# eNode_Spark.net
KiCad netlist of a schematic drawn in EAGLE
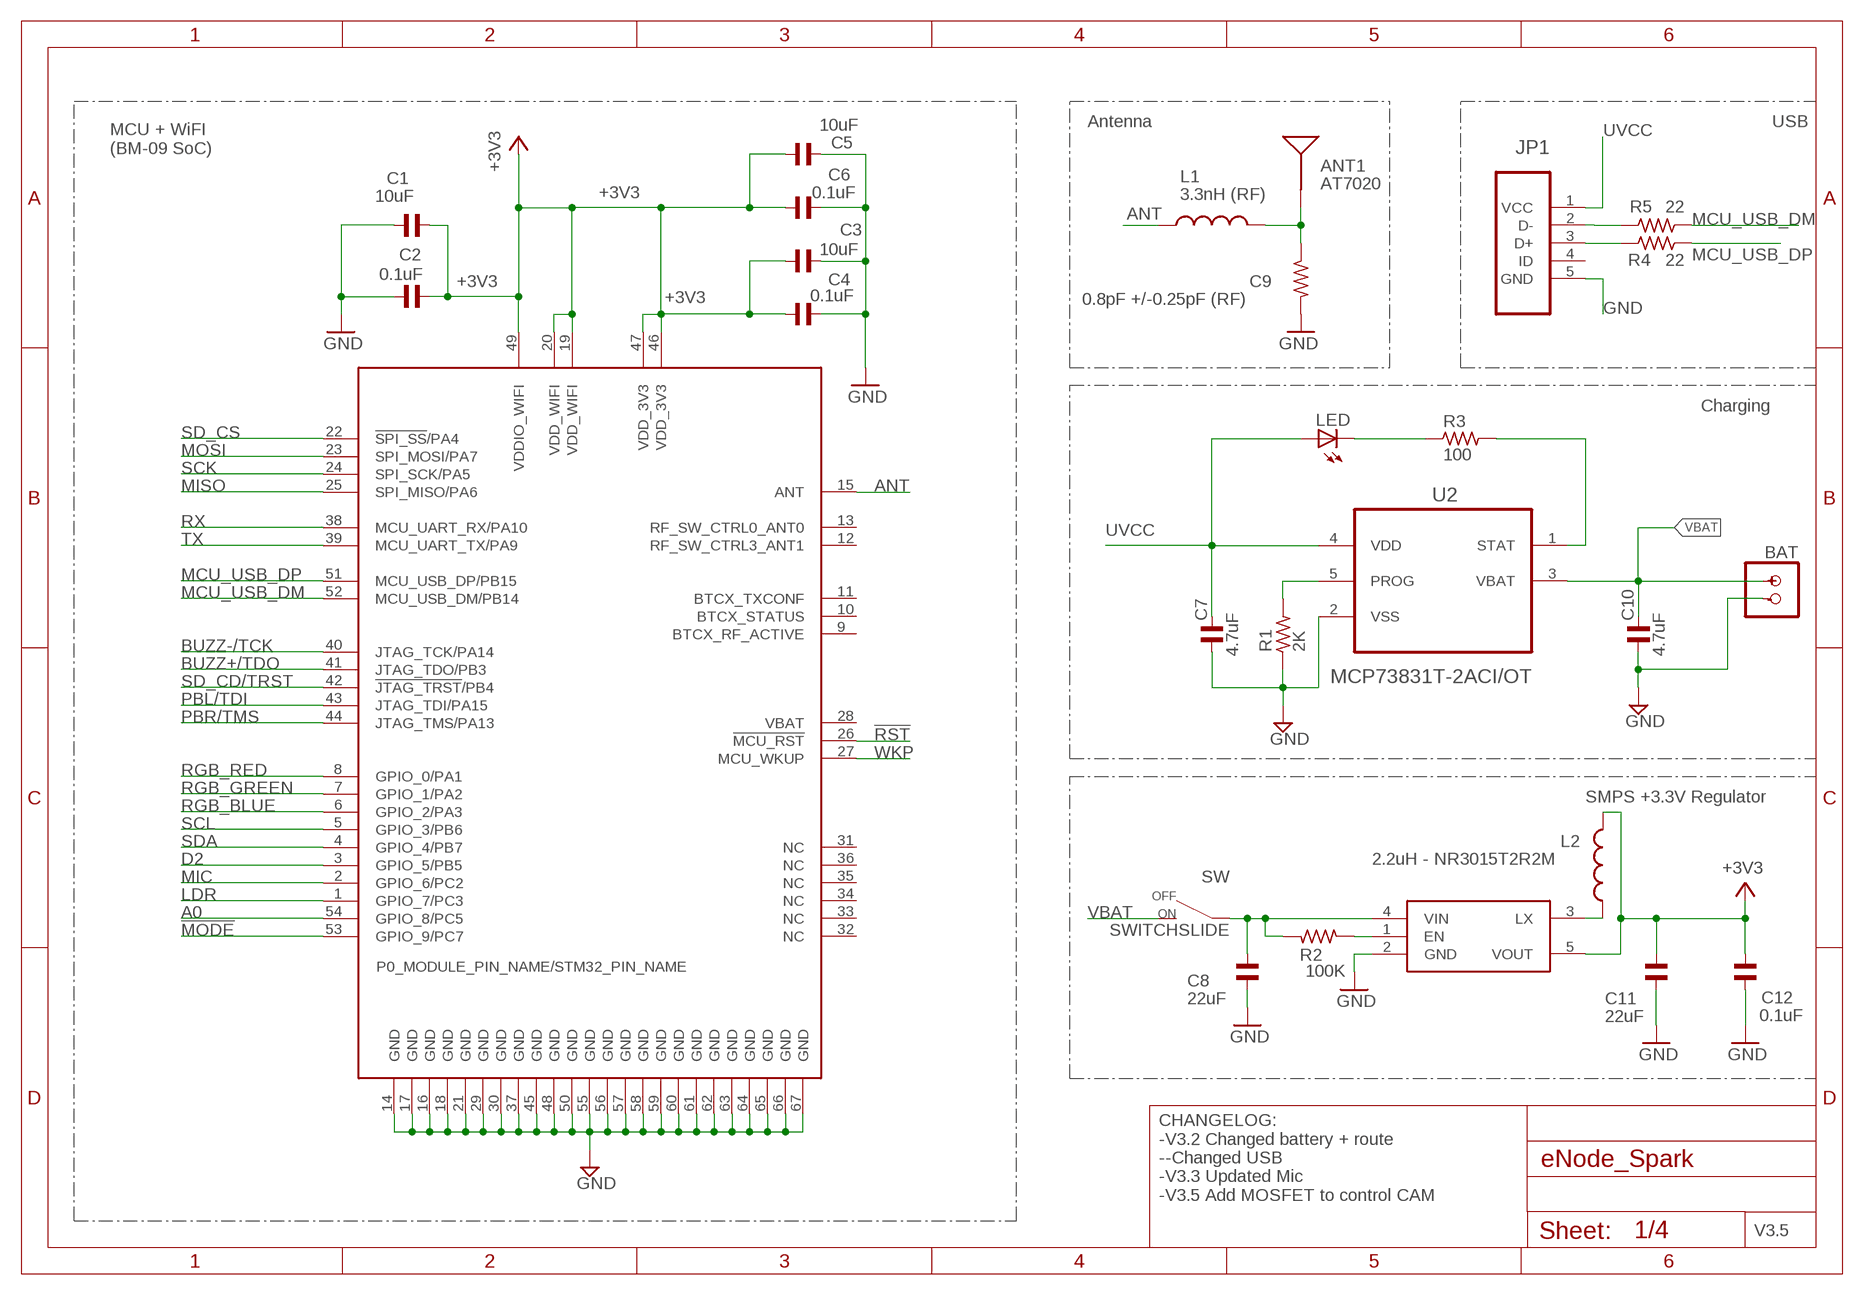
[diagram p0: schematic, sheet 1]
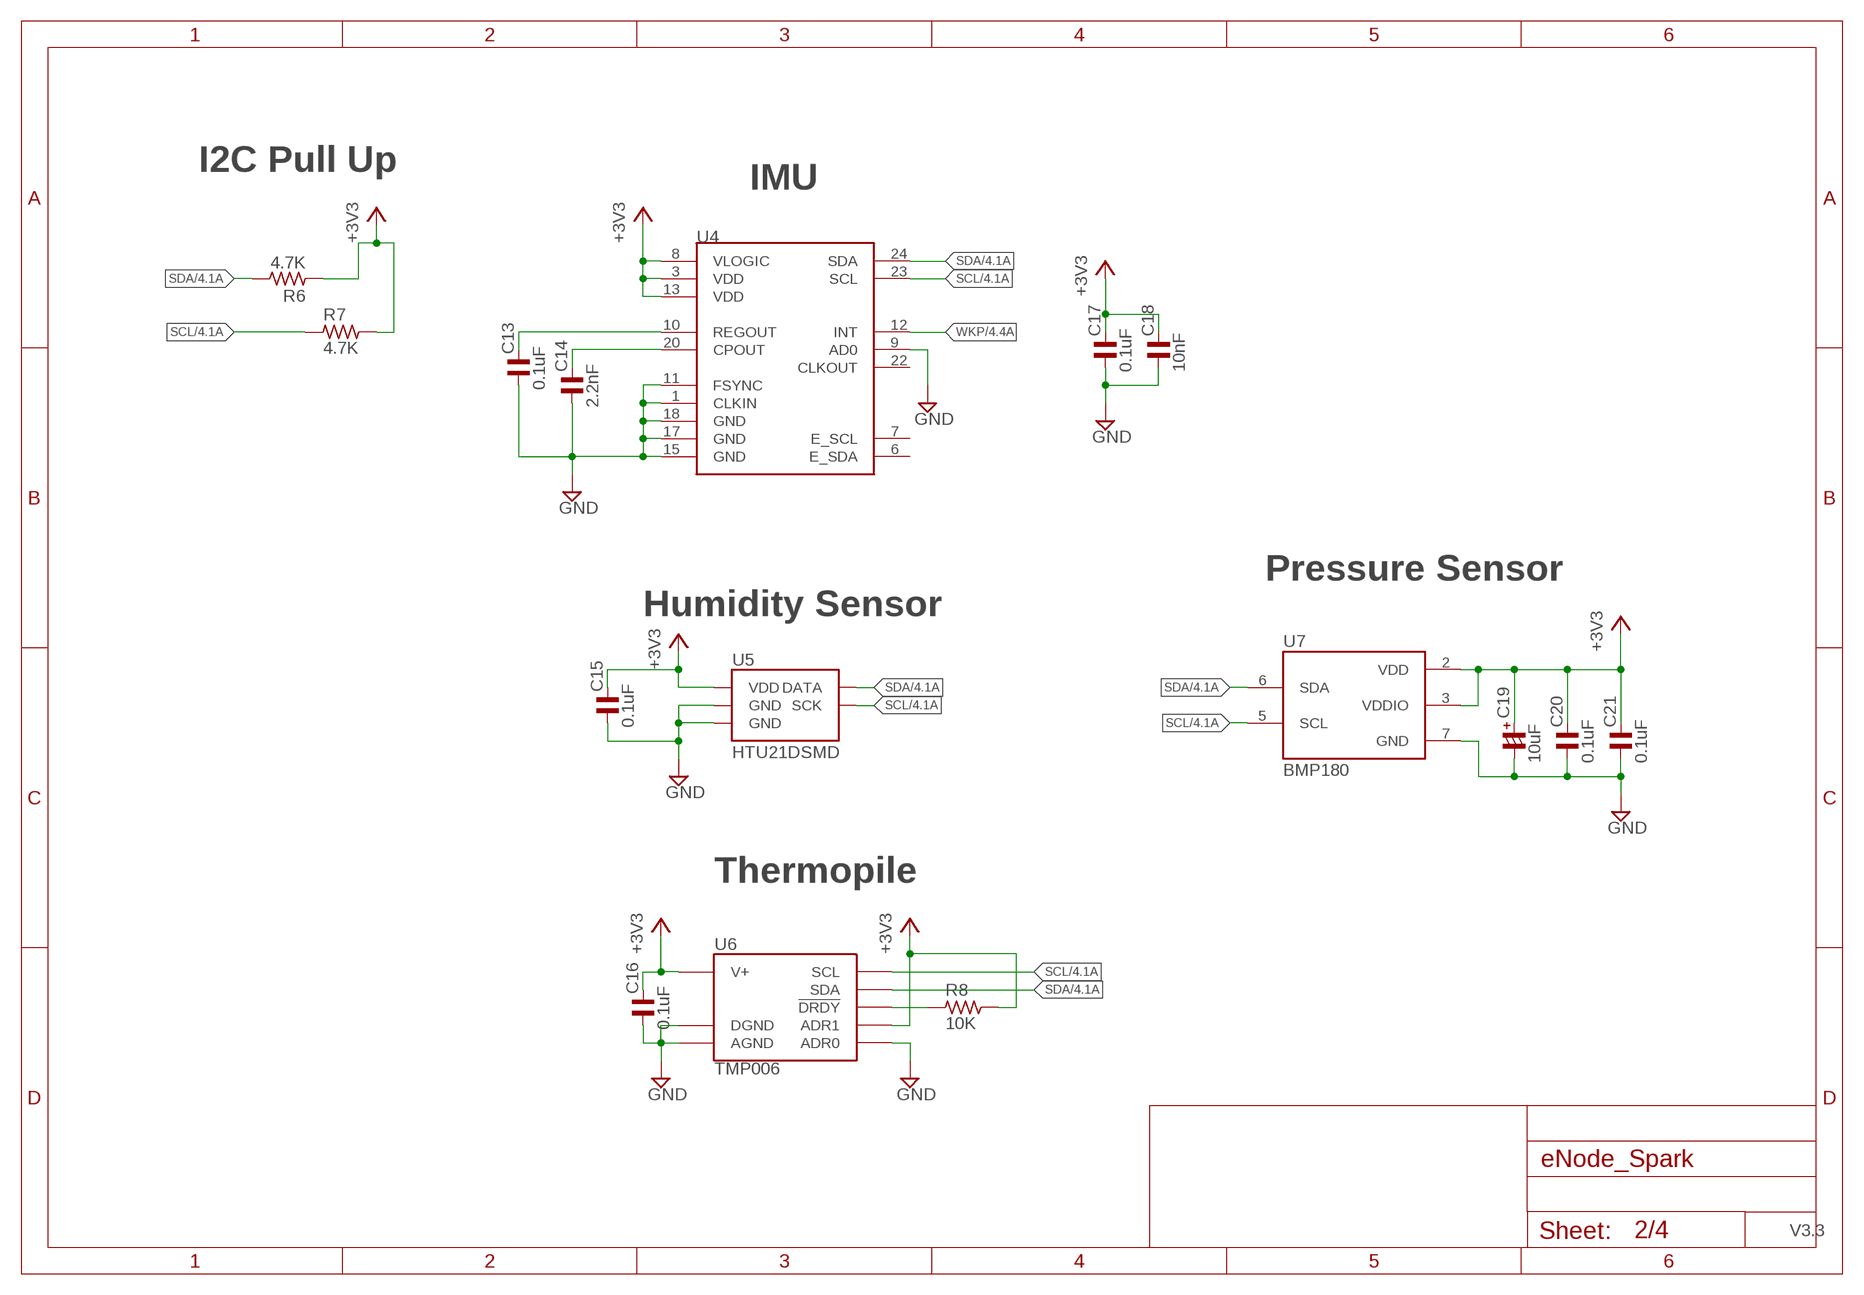
[diagram p1: schematic, sheet 2]
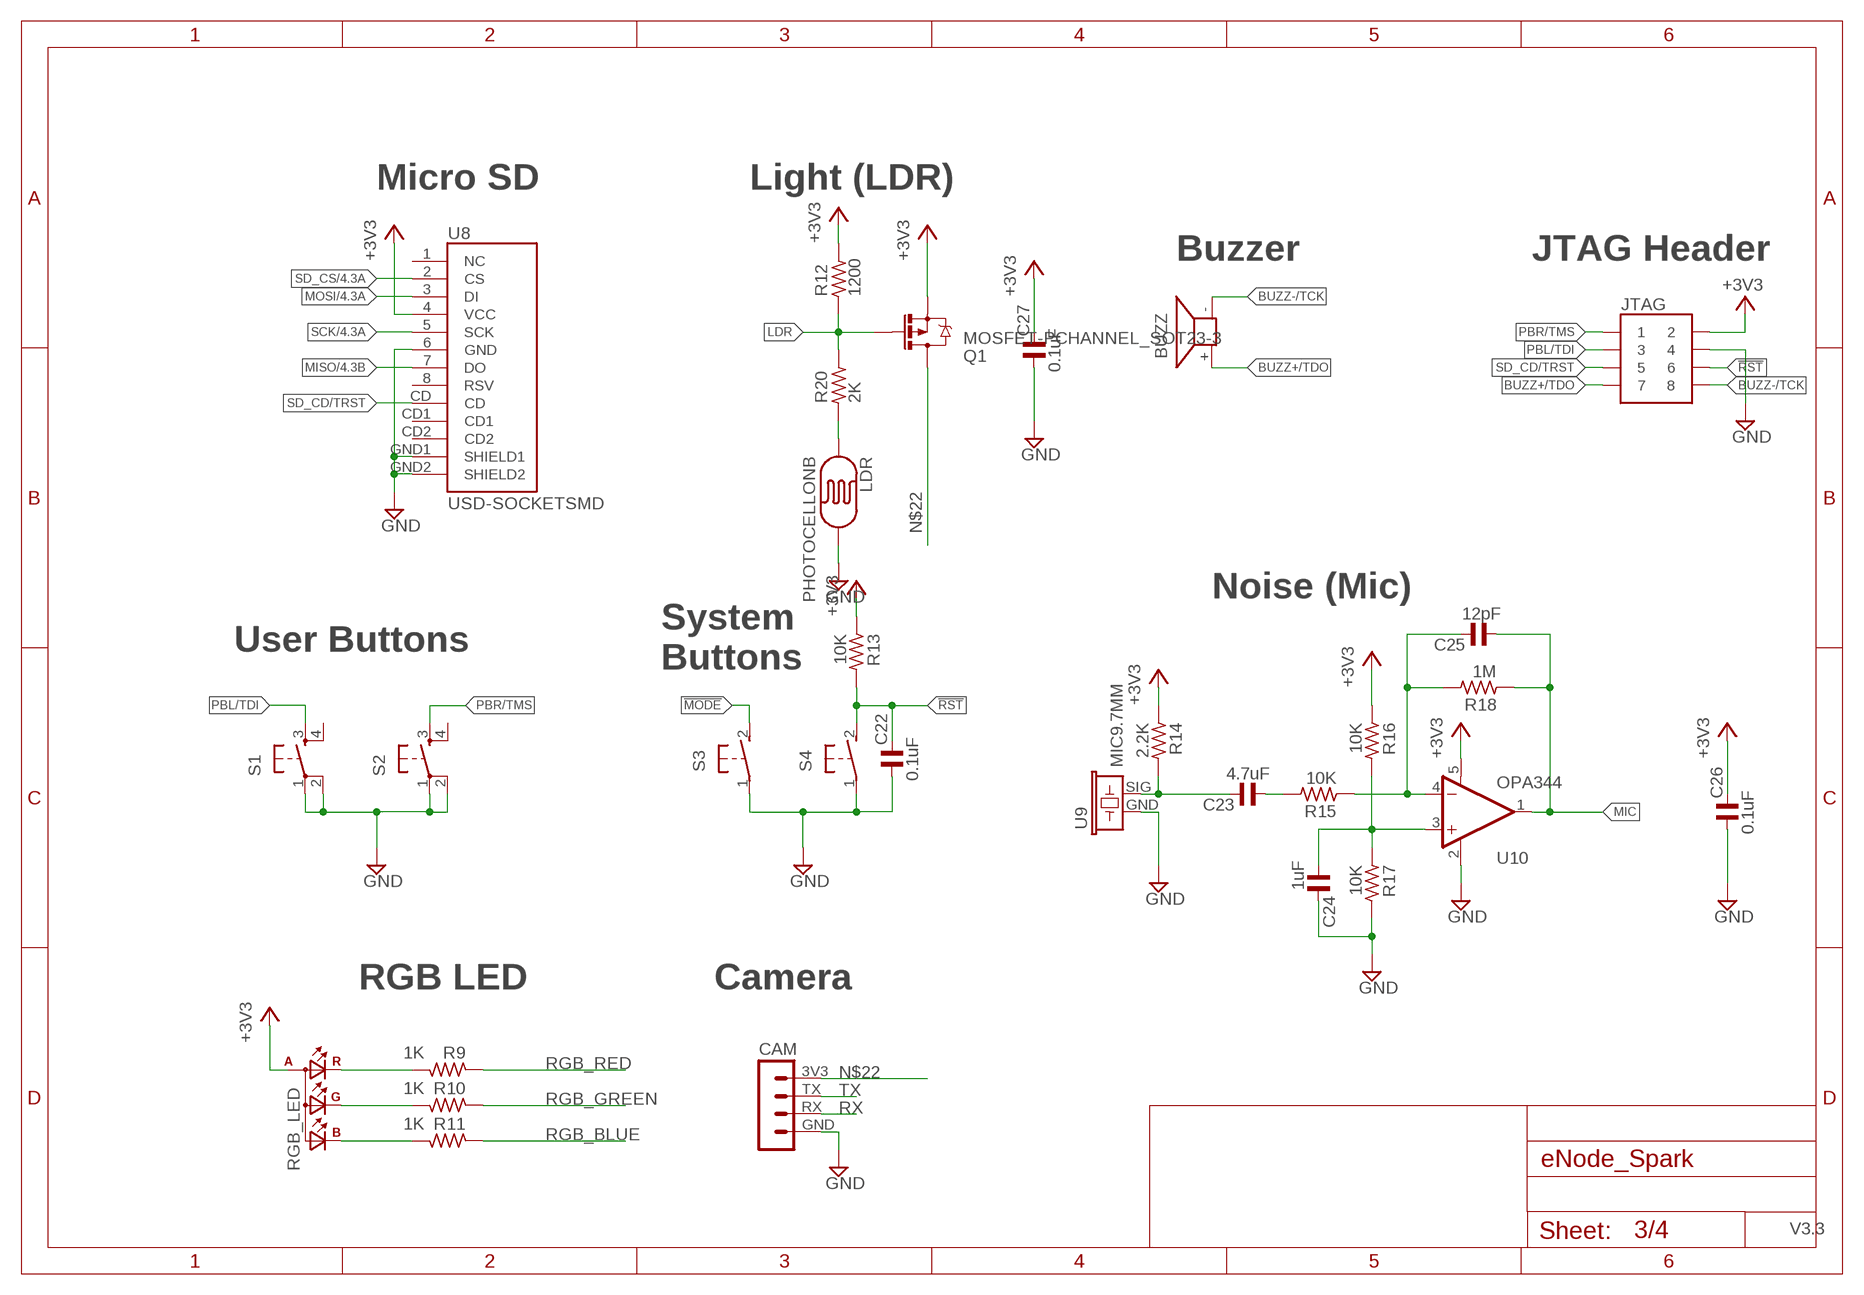
[diagram p2: schematic, sheet 3]
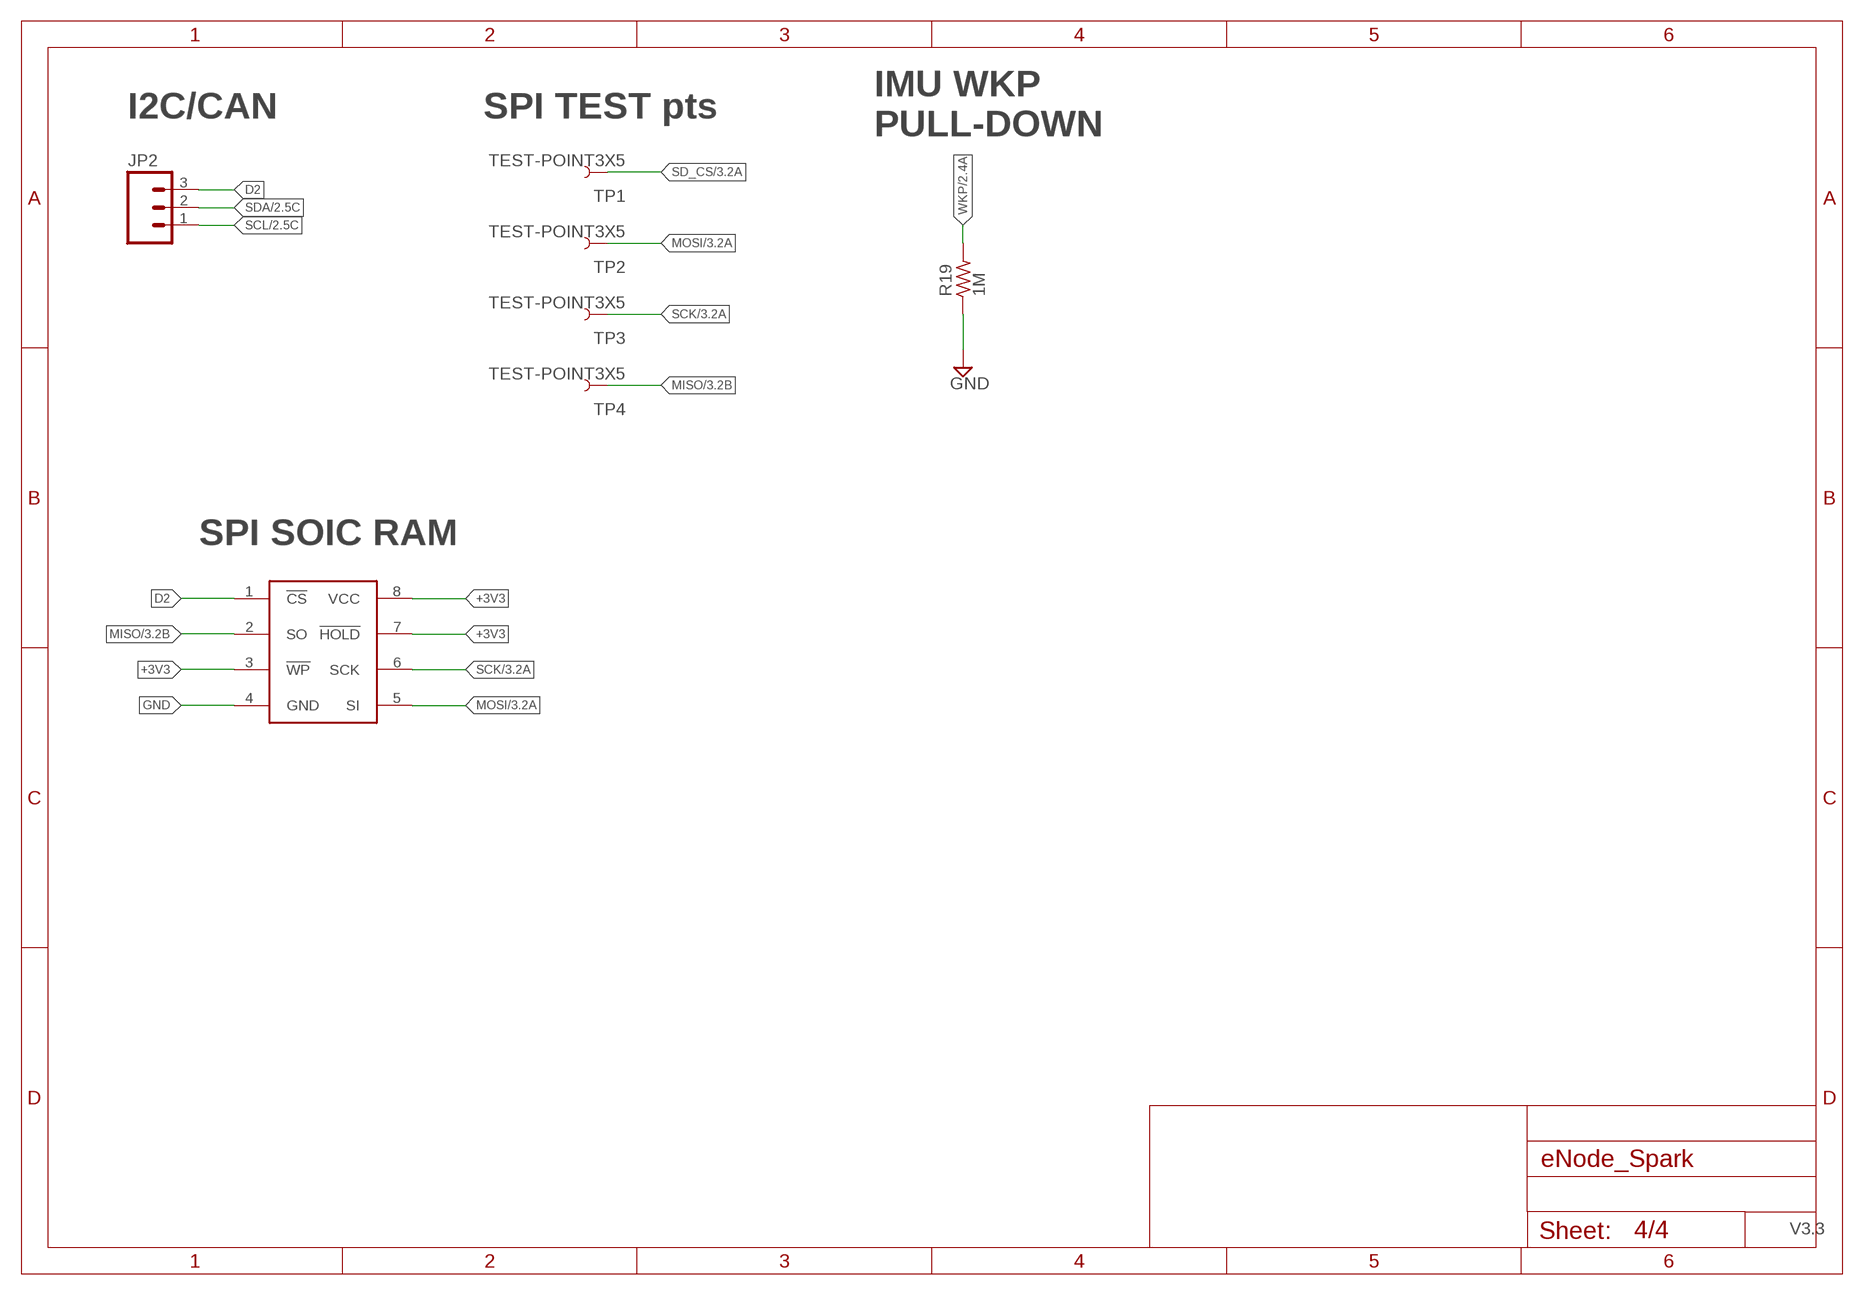
[diagram p3: schematic, sheet 4]

(export (version "E")
  (design (tool "Eeschema 10.0.6"))
  (components
    (comp (ref "JP2")
      (value "M03PTH")
      (footprint "eagle-import:1X03")
      (libsource (lib "eagle-import") (part "M03PTH"))
    )
    (comp (ref "R19")
      (value "1M")
      (footprint "eagle-import:R0402")
      (libsource (lib "eagle-import") (part "R_0402"))
    )
    (comp (ref "TP1")
      (value "TEST-POINT3X5")
      (footprint "eagle-import:PAD.03X.05")
      (libsource (lib "eagle-import") (part "TEST-POINT3X5"))
    )
    (comp (ref "TP2")
      (value "TEST-POINT3X5")
      (footprint "eagle-import:PAD.03X.05")
      (libsource (lib "eagle-import") (part "TEST-POINT3X5"))
    )
    (comp (ref "TP3")
      (value "TEST-POINT3X5")
      (footprint "eagle-import:PAD.03X.05")
      (libsource (lib "eagle-import") (part "TEST-POINT3X5"))
    )
    (comp (ref "TP4")
      (value "TEST-POINT3X5")
      (footprint "eagle-import:PAD.03X.05")
      (libsource (lib "eagle-import") (part "TEST-POINT3X5"))
    )
    (comp (ref "U11")
      (value "FRAM")
      (footprint "eagle-import:SO08")
      (libsource (lib "eagle-import") (part "FRAM"))
    )
    (comp (ref "BUZZ")
      (value "BUZZER")
      (footprint "eagle-import:OFFBOARD_NOSIGN")
      (libsource (lib "eagle-import") (part "BUZZER"))
    )
    (comp (ref "C22")
      (value "0.1uF")
      (footprint "eagle-import:C0402")
      (libsource (lib "eagle-import") (part "C_0402"))
    )
    (comp (ref "C23")
      (value "4.7uF")
      (footprint "eagle-import:C0402")
      (libsource (lib "eagle-import") (part "C_0402"))
    )
    (comp (ref "C24")
      (value "1uF")
      (footprint "eagle-import:C0402")
      (libsource (lib "eagle-import") (part "C_0402"))
    )
    (comp (ref "C25")
      (value "12pF")
      (footprint "eagle-import:C0402")
      (libsource (lib "eagle-import") (part "C_0402"))
    )
    (comp (ref "C26")
      (value "0.1uF")
      (footprint "eagle-import:C0402")
      (libsource (lib "eagle-import") (part "C_0402"))
    )
    (comp (ref "C27")
      (value "0.1uF")
      (footprint "eagle-import:C0402")
      (libsource (lib "eagle-import") (part "C_0402"))
    )
    (comp (ref "CAM")
      (value "MA04-1")
      (footprint "eagle-import:MA04-1")
      (libsource (lib "eagle-import") (part "MA04-1"))
    )
    (comp (ref "JTAG")
      (value "JTAG_CONNECTOR")
      (footprint "eagle-import:JTAG_DIP")
      (libsource (lib "eagle-import") (part "JTAG_CONNECTOR"))
    )
    (comp (ref "LDR")
      (value "PHOTOCELLONB")
      (footprint "eagle-import:ON_BOARD")
      (libsource (lib "eagle-import") (part "PHOTOCELLONB"))
    )
    (comp (ref "Q1")
      (value "MOSFET-PCHANNEL_SOT23-3")
      (footprint "eagle-import:SOT23-3")
      (libsource (lib "eagle-import") (part "MOSFET-PCHANNEL_SOT23-3"))
    )
    (comp (ref "R9")
      (value "1K")
      (footprint "eagle-import:R0402")
      (libsource (lib "eagle-import") (part "R_0402"))
    )
    (comp (ref "R10")
      (value "1K")
      (footprint "eagle-import:R0402")
      (libsource (lib "eagle-import") (part "R_0402"))
    )
    (comp (ref "R11")
      (value "1K")
      (footprint "eagle-import:R0402")
      (libsource (lib "eagle-import") (part "R_0402"))
    )
    (comp (ref "R12")
      (value "1200")
      (footprint "eagle-import:R0603")
      (libsource (lib "eagle-import") (part "R_0603"))
    )
    (comp (ref "R13")
      (value "10K")
      (footprint "eagle-import:R0402")
      (libsource (lib "eagle-import") (part "R_0402"))
    )
    (comp (ref "R14")
      (value "2.2K")
      (footprint "eagle-import:R0402")
      (libsource (lib "eagle-import") (part "R_0402"))
    )
    (comp (ref "R15")
      (value "10K")
      (footprint "eagle-import:R0402")
      (libsource (lib "eagle-import") (part "R_0402"))
    )
    (comp (ref "R16")
      (value "10K")
      (footprint "eagle-import:R0402")
      (libsource (lib "eagle-import") (part "R_0402"))
    )
    (comp (ref "R17")
      (value "10K")
      (footprint "eagle-import:R0402")
      (libsource (lib "eagle-import") (part "R_0402"))
    )
    (comp (ref "R18")
      (value "1M")
      (footprint "eagle-import:R0402")
      (libsource (lib "eagle-import") (part "R_0402"))
    )
    (comp (ref "R20")
      (value "2K")
      (footprint "eagle-import:R0603")
      (libsource (lib "eagle-import") (part "R_0603"))
    )
    (comp (ref "RGB_LED")
      (value "TOPLED-3PLCC")
      (footprint "eagle-import:P-LCC-4-3")
      (libsource (lib "eagle-import") (part "TOPLED-3PLCC"))
    )
    (comp (ref "S1")
      (value "TAC_SWITCH_4SMD")
      (footprint "eagle-import:TACTILE_SWITCH_SMD_LARGE_4")
      (libsource (lib "eagle-import") (part "TAC_SWITCH_4SMD"))
    )
    (comp (ref "S2")
      (value "TAC_SWITCH_4SMD")
      (footprint "eagle-import:TACTILE_SWITCH_SMD_LARGE_4")
      (libsource (lib "eagle-import") (part "TAC_SWITCH_4SMD"))
    )
    (comp (ref "S3")
      (value "MODE")
      (footprint "eagle-import:DTSM-3")
      (libsource (lib "eagle-import") (part "TAC_SWITCH_2MULTICOMP"))
    )
    (comp (ref "S4")
      (value "RESET")
      (footprint "eagle-import:DTSM-3")
      (libsource (lib "eagle-import") (part "TAC_SWITCH_2MULTICOMP"))
    )
    (comp (ref "U8")
      (value "USD-SOCKETSMD")
      (footprint "eagle-import:MICRO-SD-SOCKET-PP")
      (libsource (lib "eagle-import") (part "USD-SOCKETSMD"))
    )
    (comp (ref "U9")
      (value "MIC9.7MM")
      (footprint "eagle-import:MIC-9.7MM")
      (libsource (lib "eagle-import") (part "MIC9.7MM"))
    )
    (comp (ref "U10")
      (value "OPA344")
      (footprint "eagle-import:SOT23-5")
      (libsource (lib "eagle-import") (part "OPA344"))
    )
    (comp (ref "ANT1")
      (value "AT7020")
      (footprint "eagle-import:AT7020")
      (libsource (lib "eagle-import") (part "AT7020"))
    )
    (comp (ref "BAT")
      (value "BATTERYSMT")
      (footprint "eagle-import:JST-2-SMD")
      (libsource (lib "eagle-import") (part "BATTERYSMT"))
    )
    (comp (ref "C1")
      (value "10uF")
      (footprint "eagle-import:C0402")
      (libsource (lib "eagle-import") (part "C_0402"))
    )
    (comp (ref "C2")
      (value "0.1uF")
      (footprint "eagle-import:C0402")
      (libsource (lib "eagle-import") (part "C_0402"))
    )
    (comp (ref "C3")
      (value "10uF")
      (footprint "eagle-import:C0402")
      (libsource (lib "eagle-import") (part "C_0402"))
    )
    (comp (ref "C4")
      (value "0.1uF")
      (footprint "eagle-import:C0402")
      (libsource (lib "eagle-import") (part "C_0402"))
    )
    (comp (ref "C5")
      (value "10uF")
      (footprint "eagle-import:C0402")
      (libsource (lib "eagle-import") (part "C_0402"))
    )
    (comp (ref "C6")
      (value "0.1uF")
      (footprint "eagle-import:C0402")
      (libsource (lib "eagle-import") (part "C_0402"))
    )
    (comp (ref "C7")
      (value "4.7uF")
      (footprint "eagle-import:C0402")
      (libsource (lib "eagle-import") (part "C_0402"))
    )
    (comp (ref "C8")
      (value "22uF")
      (footprint "eagle-import:C0603")
      (libsource (lib "eagle-import") (part "C_0603"))
    )
    (comp (ref "C9")
      (value "0.8pF +/-0.25pF (RF)")
      (footprint "eagle-import:R0402_B")
      (libsource (lib "eagle-import") (part "R-US_"))
    )
    (comp (ref "C10")
      (value "4.7uF")
      (footprint "eagle-import:C0402")
      (libsource (lib "eagle-import") (part "C_0402"))
    )
    (comp (ref "C11")
      (value "22uF")
      (footprint "eagle-import:C0603")
      (libsource (lib "eagle-import") (part "C_0603"))
    )
    (comp (ref "C12")
      (value "0.1uF")
      (footprint "eagle-import:C0402")
      (libsource (lib "eagle-import") (part "C_0402"))
    )
    (comp (ref "JP1")
      (value "47346-0001")
      (footprint "eagle-import:MOLEX_47346-0001")
      (libsource (lib "eagle-import") (part "47346-0001"))
    )
    (comp (ref "L1")
      (value "3.3nH (RF)")
      (footprint "eagle-import:L0402_B")
      (libsource (lib "eagle-import") (part "INDUCTOR"))
    )
    (comp (ref "L2")
      (value "2.2uH - NR3015T2R2M")
      (footprint "eagle-import:INDUCTOR-NR3015")
      (libsource (lib "eagle-import") (part "INDUCTORB"))
    )
    (comp (ref "LED")
      (value "LED")
      (footprint "eagle-import:SMARTLED-TTW")
      (libsource (lib "eagle-import") (part "LED"))
    )
    (comp (ref "R1")
      (value "2K")
      (footprint "eagle-import:R0603")
      (libsource (lib "eagle-import") (part "R_0603"))
    )
    (comp (ref "R2")
      (value "100K")
      (footprint "eagle-import:R0402")
      (libsource (lib "eagle-import") (part "R_0402"))
    )
    (comp (ref "R3")
      (value "100")
      (footprint "eagle-import:R0603")
      (libsource (lib "eagle-import") (part "R_0603"))
    )
    (comp (ref "R4")
      (value "22")
      (footprint "eagle-import:R0402")
      (libsource (lib "eagle-import") (part "R_0402"))
    )
    (comp (ref "R5")
      (value "22")
      (footprint "eagle-import:R0402")
      (libsource (lib "eagle-import") (part "R_0402"))
    )
    (comp (ref "SW")
      (value "SWITCHSLIDE")
      (footprint "eagle-import:CHANGE_OVER_SLIDE")
      (libsource (lib "eagle-import") (part "SWITCHSLIDE"))
    )
    (comp (ref "U1")
      (value "WM-N-BM-09")
      (footprint "eagle-import:WM-N-BM-09")
      (libsource (lib "eagle-import") (part "WM-N-BM-09"))
    )
    (comp (ref "U2")
      (value "MCP73831T-2ACI/OT")
      (footprint "eagle-import:SOT95P280X145-5N")
      (libsource (lib "eagle-import") (part "MCP73831T-2ACI/OT"))
    )
    (comp (ref "U3")
      (value "R8008-33")
      (footprint "eagle-import:SOT23-5")
      (libsource (lib "eagle-import") (part "R8008-33"))
    )
    (comp (ref "C13")
      (value "0.1uF")
      (footprint "eagle-import:C0402")
      (libsource (lib "eagle-import") (part "C_0402"))
    )
    (comp (ref "C14")
      (value "2.2nF")
      (footprint "eagle-import:C0402")
      (libsource (lib "eagle-import") (part "C_0402"))
    )
    (comp (ref "C15")
      (value "0.1uF")
      (footprint "eagle-import:C0402")
      (libsource (lib "eagle-import") (part "C_0402"))
    )
    (comp (ref "C16")
      (value "0.1uF")
      (footprint "eagle-import:C0402")
      (libsource (lib "eagle-import") (part "C_0402"))
    )
    (comp (ref "C17")
      (value "0.1uF")
      (footprint "eagle-import:C0402")
      (libsource (lib "eagle-import") (part "C_0402"))
    )
    (comp (ref "C18")
      (value "10nF")
      (footprint "eagle-import:C0402")
      (libsource (lib "eagle-import") (part "C_0402"))
    )
    (comp (ref "C19")
      (value "10uF")
      (footprint "eagle-import:C1206_T")
      (libsource (lib "eagle-import") (part "CP_1206/T"))
    )
    (comp (ref "C20")
      (value "0.1uF")
      (footprint "eagle-import:C0402")
      (libsource (lib "eagle-import") (part "C_0402"))
    )
    (comp (ref "C21")
      (value "0.1uF")
      (footprint "eagle-import:C0402")
      (libsource (lib "eagle-import") (part "C_0402"))
    )
    (comp (ref "R6")
      (value "4.7K")
      (footprint "eagle-import:R0402")
      (libsource (lib "eagle-import") (part "R_0402"))
    )
    (comp (ref "R7")
      (value "4.7K")
      (footprint "eagle-import:R0402")
      (libsource (lib "eagle-import") (part "R_0402"))
    )
    (comp (ref "R8")
      (value "10K")
      (footprint "eagle-import:R0603")
      (libsource (lib "eagle-import") (part "R_0603"))
    )
    (comp (ref "U4")
      (value "MPU-9150QFN-24-NP")
      (footprint "eagle-import:QFN-24-NP")
      (libsource (lib "eagle-import") (part "MPU-9150QFN-24-NP"))
    )
    (comp (ref "U5")
      (value "HTU21DSMD")
      (footprint "eagle-import:HTU21D")
      (libsource (lib "eagle-import") (part "HTU21DSMD"))
    )
    (comp (ref "U6")
      (value "TMP006")
      (footprint "eagle-import:BGA8DS")
      (libsource (lib "eagle-import") (part "TMP006"))
    )
    (comp (ref "U7")
      (value "BMP180")
      (footprint "eagle-import:BMP180")
      (libsource (lib "eagle-import") (part "BMP180"))
    )
  )
  (nets
    (net (code "1") (name "+3V3") (class "Default")
      (node (ref "C1") (pin "2") (pinfunction "2_2") (pintype "passive"))
      (node (ref "C11") (pin "1") (pinfunction "1_1") (pintype "passive"))
      (node (ref "C12") (pin "1") (pinfunction "1_1") (pintype "passive"))
      (node (ref "C15") (pin "2") (pinfunction "2_2") (pintype "passive"))
      (node (ref "C16") (pin "2") (pinfunction "2_2") (pintype "passive"))
      (node (ref "C17") (pin "2") (pinfunction "2_2") (pintype "passive"))
      (node (ref "C18") (pin "2") (pinfunction "2_2") (pintype "passive"))
      (node (ref "C19") (pin "+") (pinfunction "+_+") (pintype "passive"))
      (node (ref "C2") (pin "2") (pinfunction "2_2") (pintype "passive"))
      (node (ref "C20") (pin "2") (pinfunction "2_2") (pintype "passive"))
      (node (ref "C21") (pin "2") (pinfunction "2_2") (pintype "passive"))
      (node (ref "C26") (pin "2") (pinfunction "2_2") (pintype "passive"))
      (node (ref "C27") (pin "2") (pinfunction "2_2") (pintype "passive"))
      (node (ref "C3") (pin "1") (pinfunction "1_1") (pintype "passive"))
      (node (ref "C4") (pin "2") (pinfunction "2_2") (pintype "passive"))
      (node (ref "C5") (pin "1") (pinfunction "1_1") (pintype "passive"))
      (node (ref "C6") (pin "2") (pinfunction "2_2") (pintype "passive"))
      (node (ref "JTAG") (pin "2") (pinfunction "2_2") (pintype "bidirectional"))
      (node (ref "L2") (pin "2") (pinfunction "2_2") (pintype "passive"))
      (node (ref "Q1") (pin "2") (pinfunction "S_2") (pintype "passive"))
      (node (ref "R12") (pin "2") (pinfunction "2_2") (pintype "passive"))
      (node (ref "R13") (pin "1") (pinfunction "1_1") (pintype "passive"))
      (node (ref "R14") (pin "1") (pinfunction "1_1") (pintype "passive"))
      (node (ref "R16") (pin "1") (pinfunction "1_1") (pintype "passive"))
      (node (ref "R6") (pin "1") (pinfunction "1_1") (pintype "passive"))
      (node (ref "R7") (pin "2") (pinfunction "2_2") (pintype "passive"))
      (node (ref "R8") (pin "2") (pinfunction "2_2") (pintype "passive"))
      (node (ref "RGB_LED") (pin "A") (pinfunction "A2_A") (pintype "passive"))
      (node (ref "U1") (pin "19") (pinfunction "VDD_WIFI_19") (pintype "bidirectional"))
      (node (ref "U1") (pin "20") (pinfunction "VDD_WIFI_20") (pintype "bidirectional"))
      (node (ref "U1") (pin "46") (pinfunction "VDD_3V3_46") (pintype "bidirectional"))
      (node (ref "U1") (pin "47") (pinfunction "VDD_3V3_47") (pintype "bidirectional"))
      (node (ref "U1") (pin "49") (pinfunction "VDDIO_WIFI_49") (pintype "bidirectional"))
      (node (ref "U10") (pin "5") (pinfunction "V+_5") (pintype "power_in"))
      (node (ref "U11") (pin "3") (pinfunction "~{WP}_3") (pintype "bidirectional"))
      (node (ref "U11") (pin "7") (pinfunction "~{HOLD}_7") (pintype "bidirectional"))
      (node (ref "U11") (pin "8") (pinfunction "VCC_8") (pintype "bidirectional"))
      (node (ref "U3") (pin "5") (pinfunction "VOUT_5") (pintype "bidirectional"))
      (node (ref "U4") (pin "13") (pinfunction "VDD_13") (pintype "bidirectional"))
      (node (ref "U4") (pin "3") (pinfunction "VDD_3") (pintype "bidirectional"))
      (node (ref "U4") (pin "8") (pinfunction "VLOGIC_8") (pintype "bidirectional"))
      (node (ref "U5") (pin "VDD") (pinfunction "VDD_VDD") (pintype "power_in"))
      (node (ref "U6") (pin "A3") (pinfunction "V+_A3") (pintype "bidirectional"))
      (node (ref "U6") (pin "B1") (pinfunction "ADR1_B1") (pintype "bidirectional"))
      (node (ref "U7") (pin "2") (pinfunction "VDD_2") (pintype "power_in"))
      (node (ref "U7") (pin "3") (pinfunction "VDDIO_3") (pintype "power_in"))
      (node (ref "U8") (pin "4") (pinfunction "VCC_4") (pintype "bidirectional"))
    )
    (net (code "2") (name "A0") (class "Default")
      (node (ref "U1") (pin "54") (pinfunction "GPIO_8/PC5_54") (pintype "bidirectional"))
    )
    (net (code "3") (name "ANT") (class "Default")
      (node (ref "L1") (pin "1") (pinfunction "1_1") (pintype "passive"))
      (node (ref "U1") (pin "15") (pinfunction "ANT_15") (pintype "bidirectional"))
    )
    (net (code "4") (name "BUZZ+{slash}TDO") (class "Default")
      (node (ref "BUZZ") (pin "+") (pinfunction "+_+") (pintype "passive"))
      (node (ref "JTAG") (pin "7") (pinfunction "7_7") (pintype "bidirectional"))
      (node (ref "U1") (pin "41") (pinfunction "JTAG_TDO/PB3_41") (pintype "bidirectional"))
    )
    (net (code "5") (name "BUZZ-{slash}TCK") (class "Default")
      (node (ref "BUZZ") (pin "-") (pinfunction "-_-") (pintype "passive"))
      (node (ref "JTAG") (pin "8") (pinfunction "8_8") (pintype "bidirectional"))
      (node (ref "U1") (pin "40") (pinfunction "JTAG_TCK/PA14_40") (pintype "bidirectional"))
    )
    (net (code "6") (name "D2") (class "Default")
      (node (ref "JP2") (pin "3") (pinfunction "3_3") (pintype "passive"))
      (node (ref "U1") (pin "3") (pinfunction "GPIO_5/PB5_3") (pintype "bidirectional"))
      (node (ref "U11") (pin "1") (pinfunction "~{CS}_1") (pintype "bidirectional"))
    )
    (net (code "7") (name "GND") (class "Default")
      (node (ref "BAT") (pin "-") (pinfunction "-_-") (pintype "passive"))
      (node (ref "C1") (pin "1") (pinfunction "1_1") (pintype "passive"))
      (node (ref "C10") (pin "1") (pinfunction "1_1") (pintype "passive"))
      (node (ref "C11") (pin "2") (pinfunction "2_2") (pintype "passive"))
      (node (ref "C12") (pin "2") (pinfunction "2_2") (pintype "passive"))
      (node (ref "C13") (pin "1") (pinfunction "1_1") (pintype "passive"))
      (node (ref "C14") (pin "1") (pinfunction "1_1") (pintype "passive"))
      (node (ref "C15") (pin "1") (pinfunction "1_1") (pintype "passive"))
      (node (ref "C16") (pin "1") (pinfunction "1_1") (pintype "passive"))
      (node (ref "C17") (pin "1") (pinfunction "1_1") (pintype "passive"))
      (node (ref "C18") (pin "1") (pinfunction "1_1") (pintype "passive"))
      (node (ref "C19") (pin "-") (pinfunction "-_-") (pintype "passive"))
      (node (ref "C2") (pin "1") (pinfunction "1_1") (pintype "passive"))
      (node (ref "C20") (pin "1") (pinfunction "1_1") (pintype "passive"))
      (node (ref "C21") (pin "1") (pinfunction "1_1") (pintype "passive"))
      (node (ref "C22") (pin "1") (pinfunction "1_1") (pintype "passive"))
      (node (ref "C24") (pin "2") (pinfunction "2_2") (pintype "passive"))
      (node (ref "C26") (pin "1") (pinfunction "1_1") (pintype "passive"))
      (node (ref "C27") (pin "1") (pinfunction "1_1") (pintype "passive"))
      (node (ref "C3") (pin "2") (pinfunction "2_2") (pintype "passive"))
      (node (ref "C4") (pin "1") (pinfunction "1_1") (pintype "passive"))
      (node (ref "C5") (pin "2") (pinfunction "2_2") (pintype "passive"))
      (node (ref "C6") (pin "1") (pinfunction "1_1") (pintype "passive"))
      (node (ref "C7") (pin "1") (pinfunction "1_1") (pintype "passive"))
      (node (ref "C8") (pin "2") (pinfunction "2_2") (pintype "passive"))
      (node (ref "C9") (pin "2") (pinfunction "2_2") (pintype "passive"))
      (node (ref "CAM") (pin "GND") (pinfunction "GND_GND") (pintype "passive"))
      (node (ref "JP1") (pin "5") (pinfunction "GND_5") (pintype "input"))
      (node (ref "JTAG") (pin "4") (pinfunction "4_4") (pintype "bidirectional"))
      (node (ref "LDR") (pin "2") (pinfunction "P$2_2") (pintype "bidirectional"))
      (node (ref "R1") (pin "1") (pinfunction "1_1") (pintype "passive"))
      (node (ref "R17") (pin "2") (pinfunction "2_2") (pintype "passive"))
      (node (ref "R19") (pin "1") (pinfunction "1_1") (pintype "passive"))
      (node (ref "S1") (pin "1") (pinfunction "1_1") (pintype "passive"))
      (node (ref "S1") (pin "2") (pinfunction "2_2") (pintype "passive"))
      (node (ref "S2") (pin "1") (pinfunction "1_1") (pintype "passive"))
      (node (ref "S2") (pin "2") (pinfunction "2_2") (pintype "passive"))
      (node (ref "S3") (pin "1") (pinfunction "1_1") (pintype "passive"))
      (node (ref "S4") (pin "1") (pinfunction "1_1") (pintype "passive"))
      (node (ref "U1") (pin "14") (pinfunction "GND_14") (pintype "bidirectional"))
      (node (ref "U1") (pin "16") (pinfunction "GND_16") (pintype "bidirectional"))
      (node (ref "U1") (pin "17") (pinfunction "GND_17") (pintype "bidirectional"))
      (node (ref "U1") (pin "18") (pinfunction "GND_18") (pintype "bidirectional"))
      (node (ref "U1") (pin "21") (pinfunction "GND_21") (pintype "bidirectional"))
      (node (ref "U1") (pin "29") (pinfunction "GND_29") (pintype "bidirectional"))
      (node (ref "U1") (pin "30") (pinfunction "GND_30") (pintype "bidirectional"))
      (node (ref "U1") (pin "37") (pinfunction "GND_37") (pintype "bidirectional"))
      (node (ref "U1") (pin "45") (pinfunction "GND_45") (pintype "bidirectional"))
      (node (ref "U1") (pin "48") (pinfunction "GND_48") (pintype "bidirectional"))
      (node (ref "U1") (pin "50") (pinfunction "GND_50") (pintype "bidirectional"))
      (node (ref "U1") (pin "55") (pinfunction "GND_55") (pintype "bidirectional"))
      (node (ref "U1") (pin "56") (pinfunction "GND_56") (pintype "bidirectional"))
      (node (ref "U1") (pin "57") (pinfunction "GND_57") (pintype "bidirectional"))
      (node (ref "U1") (pin "58") (pinfunction "GND_58") (pintype "bidirectional"))
      (node (ref "U1") (pin "59") (pinfunction "GND_59") (pintype "bidirectional"))
      (node (ref "U1") (pin "60") (pinfunction "GND_60") (pintype "bidirectional"))
      (node (ref "U1") (pin "61") (pinfunction "GND_61") (pintype "bidirectional"))
      (node (ref "U1") (pin "62") (pinfunction "GND_62") (pintype "bidirectional"))
      (node (ref "U1") (pin "63") (pinfunction "GND_63") (pintype "bidirectional"))
      (node (ref "U1") (pin "64") (pinfunction "GND_64") (pintype "bidirectional"))
      (node (ref "U1") (pin "65") (pinfunction "GND_65") (pintype "bidirectional"))
      (node (ref "U1") (pin "66") (pinfunction "GND_66") (pintype "bidirectional"))
      (node (ref "U1") (pin "67") (pinfunction "GND_67") (pintype "bidirectional"))
      (node (ref "U10") (pin "2") (pinfunction "V-_2") (pintype "power_in"))
      (node (ref "U11") (pin "4") (pinfunction "GND_4") (pintype "bidirectional"))
      (node (ref "U2") (pin "2") (pinfunction "VSS_2") (pintype "power_in"))
      (node (ref "U3") (pin "2") (pinfunction "GND_2") (pintype "bidirectional"))
      (node (ref "U4") (pin "1") (pinfunction "CLKIN_1") (pintype "bidirectional"))
      (node (ref "U4") (pin "11") (pinfunction "FSYNC_11") (pintype "bidirectional"))
      (node (ref "U4") (pin "15") (pinfunction "GND_15") (pintype "bidirectional"))
      (node (ref "U4") (pin "17") (pinfunction "GND_17") (pintype "bidirectional"))
      (node (ref "U4") (pin "18") (pinfunction "GND_18") (pintype "bidirectional"))
      (node (ref "U4") (pin "9") (pinfunction "AD0_9") (pintype "bidirectional"))
      (node (ref "U5") (pin "7") (pinfunction "GND_7") (pintype "power_in"))
      (node (ref "U5") (pin "GND") (pinfunction "GND_GND") (pintype "power_in"))
      (node (ref "U6") (pin "A1") (pinfunction "DGND_A1") (pintype "bidirectional"))
      (node (ref "U6") (pin "A2") (pinfunction "AGND_A2") (pintype "bidirectional"))
      (node (ref "U6") (pin "C1") (pinfunction "ADR0_C1") (pintype "bidirectional"))
      (node (ref "U7") (pin "7") (pinfunction "GND_7") (pintype "power_in"))
      (node (ref "U8") (pin "6") (pinfunction "GND_6") (pintype "bidirectional"))
      (node (ref "U8") (pin "GND1") (pinfunction "SHIELD1_GND1") (pintype "bidirectional"))
      (node (ref "U8") (pin "GND2") (pinfunction "SHIELD2_GND2") (pintype "bidirectional"))
      (node (ref "U9") (pin "GND") (pinfunction "GND_GND") (pintype "passive"))
    )
    (net (code "8") (name "LDR") (class "Default")
      (node (ref "Q1") (pin "1") (pinfunction "G_1") (pintype "passive"))
      (node (ref "R12") (pin "1") (pinfunction "1_1") (pintype "passive"))
      (node (ref "R20") (pin "2") (pinfunction "2_2") (pintype "passive"))
      (node (ref "U1") (pin "1") (pinfunction "GPIO_7/PC3_1") (pintype "bidirectional"))
    )
    (net (code "9") (name "MCU_USB_DM") (class "Default")
      (node (ref "R5") (pin "1") (pinfunction "1_1") (pintype "passive"))
      (node (ref "U1") (pin "52") (pinfunction "MCU_USB_DM/PB14_52") (pintype "bidirectional"))
    )
    (net (code "10") (name "MCU_USB_DP") (class "Default")
      (node (ref "R4") (pin "1") (pinfunction "1_1") (pintype "passive"))
      (node (ref "U1") (pin "51") (pinfunction "MCU_USB_DP/PB15_51") (pintype "bidirectional"))
    )
    (net (code "11") (name "MIC") (class "Default")
      (node (ref "C25") (pin "1") (pinfunction "1_1") (pintype "passive"))
      (node (ref "R18") (pin "1") (pinfunction "1_1") (pintype "passive"))
      (node (ref "U1") (pin "2") (pinfunction "GPIO_6/PC2_2") (pintype "bidirectional"))
      (node (ref "U10") (pin "1") (pinfunction "OUT_1") (pintype "output"))
    )
    (net (code "12") (name "MISO") (class "Default")
      (node (ref "TP4") (pin "P$1") (pinfunction "1_P$1") (pintype "bidirectional"))
      (node (ref "U1") (pin "25") (pinfunction "SPI_MISO/PA6_25") (pintype "bidirectional"))
      (node (ref "U11") (pin "2") (pinfunction "SO_2") (pintype "bidirectional"))
      (node (ref "U8") (pin "7") (pinfunction "DO_7") (pintype "bidirectional"))
    )
    (net (code "13") (name "MOSI") (class "Default")
      (node (ref "TP2") (pin "P$1") (pinfunction "1_P$1") (pintype "bidirectional"))
      (node (ref "U1") (pin "23") (pinfunction "SPI_MOSI/PA7_23") (pintype "bidirectional"))
      (node (ref "U11") (pin "5") (pinfunction "SI_5") (pintype "bidirectional"))
      (node (ref "U8") (pin "3") (pinfunction "DI_3") (pintype "bidirectional"))
    )
    (net (code "14") (name "N$22") (class "Default")
      (node (ref "CAM") (pin "3V3") (pinfunction "3V3_3V3") (pintype "passive"))
      (node (ref "Q1") (pin "3") (pinfunction "D_3") (pintype "passive"))
    )
    (net (code "15") (name "Net-(ANT1-SIGNAL)") (class "Default")
      (node (ref "ANT1") (pin "1") (pinfunction "SIGNAL_1") (pintype "bidirectional"))
      (node (ref "C9") (pin "1") (pinfunction "1_1") (pintype "passive"))
      (node (ref "L1") (pin "2") (pinfunction "2_2") (pintype "passive"))
    )
    (net (code "16") (name "Net-(C23-Pad1)") (class "Default")
      (node (ref "C23") (pin "1") (pinfunction "1_1") (pintype "passive"))
      (node (ref "R15") (pin "2") (pinfunction "2_2") (pintype "passive"))
    )
    (net (code "17") (name "Net-(C23-Pad2)") (class "Default")
      (node (ref "C23") (pin "2") (pinfunction "2_2") (pintype "passive"))
      (node (ref "R14") (pin "2") (pinfunction "2_2") (pintype "passive"))
      (node (ref "U9") (pin "SIG") (pinfunction "SIG_SIG") (pintype "passive"))
    )
    (net (code "18") (name "Net-(JP1-D+)") (class "Default")
      (node (ref "JP1") (pin "3") (pinfunction "D+_3") (pintype "input"))
      (node (ref "R4") (pin "2") (pinfunction "2_2") (pintype "passive"))
    )
    (net (code "19") (name "Net-(JP1-D-)") (class "Default")
      (node (ref "JP1") (pin "2") (pinfunction "D-_2") (pintype "input"))
      (node (ref "R5") (pin "2") (pinfunction "2_2") (pintype "passive"))
    )
    (net (code "20") (name "Net-(LDR-P$1)") (class "Default")
      (node (ref "LDR") (pin "1") (pinfunction "P$1_1") (pintype "bidirectional"))
      (node (ref "R20") (pin "1") (pinfunction "1_1") (pintype "passive"))
    )
    (net (code "21") (name "Net-(LED-C)") (class "Default")
      (node (ref "LED") (pin "C@1") (pinfunction "C_C@1") (pintype "passive"))
      (node (ref "R3") (pin "1") (pinfunction "1_1") (pintype "passive"))
    )
    (net (code "22") (name "Net-(RGB_LED-CBLUE)") (class "Default")
      (node (ref "R11") (pin "1") (pinfunction "1_1") (pintype "passive"))
      (node (ref "RGB_LED") (pin "B") (pinfunction "CBLUE_B") (pintype "passive"))
    )
    (net (code "23") (name "Net-(RGB_LED-CGREEN)") (class "Default")
      (node (ref "R10") (pin "1") (pinfunction "1_1") (pintype "passive"))
      (node (ref "RGB_LED") (pin "G") (pinfunction "CGREEN_G") (pintype "passive"))
    )
    (net (code "24") (name "Net-(RGB_LED-CRED)") (class "Default")
      (node (ref "R9") (pin "1") (pinfunction "1_1") (pintype "passive"))
      (node (ref "RGB_LED") (pin "R") (pinfunction "CRED_R") (pintype "passive"))
    )
    (net (code "25") (name "Net-(U2-PROG)") (class "Default")
      (node (ref "R1") (pin "2") (pinfunction "2_2") (pintype "passive"))
      (node (ref "U2") (pin "5") (pinfunction "PROG_5") (pintype "input"))
    )
    (net (code "26") (name "Net-(U2-STAT)") (class "Default")
      (node (ref "R3") (pin "2") (pinfunction "2_2") (pintype "passive"))
      (node (ref "U2") (pin "1") (pinfunction "STAT_1") (pintype "output"))
    )
    (net (code "27") (name "Net-(U3-EN)") (class "Default")
      (node (ref "R2") (pin "1") (pinfunction "1_1") (pintype "passive"))
      (node (ref "U3") (pin "1") (pinfunction "EN_1") (pintype "bidirectional"))
    )
    (net (code "28") (name "Net-(U3-LX)") (class "Default")
      (node (ref "L2") (pin "1") (pinfunction "1_1") (pintype "passive"))
      (node (ref "U3") (pin "3") (pinfunction "LX_3") (pintype "bidirectional"))
    )
    (net (code "29") (name "Net-(U3-VIN)") (class "Default")
      (node (ref "C8") (pin "1") (pinfunction "1_1") (pintype "passive"))
      (node (ref "R2") (pin "2") (pinfunction "2_2") (pintype "passive"))
      (node (ref "SW") (pin "1") (pinfunction "1_1") (pintype "bidirectional"))
      (node (ref "U3") (pin "4") (pinfunction "VIN_4") (pintype "bidirectional"))
    )
    (net (code "30") (name "Net-(U4-CPOUT)") (class "Default")
      (node (ref "C14") (pin "2") (pinfunction "2_2") (pintype "passive"))
      (node (ref "U4") (pin "20") (pinfunction "CPOUT_20") (pintype "bidirectional"))
    )
    (net (code "31") (name "Net-(U4-REGOUT)") (class "Default")
      (node (ref "C13") (pin "2") (pinfunction "2_2") (pintype "passive"))
      (node (ref "U4") (pin "10") (pinfunction "REGOUT_10") (pintype "bidirectional"))
    )
    (net (code "32") (name "Net-(U6-~{DRDY})") (class "Default")
      (node (ref "R8") (pin "1") (pinfunction "1_1") (pintype "passive"))
      (node (ref "U6") (pin "C2") (pinfunction "~{DRDY}_C2") (pintype "bidirectional"))
    )
    (net (code "33") (name "Net-(U10-+IN)") (class "Default")
      (node (ref "C24") (pin "1") (pinfunction "1_1") (pintype "passive"))
      (node (ref "R16") (pin "2") (pinfunction "2_2") (pintype "passive"))
      (node (ref "R17") (pin "1") (pinfunction "1_1") (pintype "passive"))
      (node (ref "U10") (pin "3") (pinfunction "+IN_3") (pintype "input"))
    )
    (net (code "34") (name "Net-(U10--IN)") (class "Default")
      (node (ref "C25") (pin "2") (pinfunction "2_2") (pintype "passive"))
      (node (ref "R15") (pin "1") (pinfunction "1_1") (pintype "passive"))
      (node (ref "R18") (pin "2") (pinfunction "2_2") (pintype "passive"))
      (node (ref "U10") (pin "4") (pinfunction "-IN_4") (pintype "input"))
    )
    (net (code "35") (name "PBL{slash}TDI") (class "Default")
      (node (ref "JTAG") (pin "3") (pinfunction "3_3") (pintype "bidirectional"))
      (node (ref "S1") (pin "3") (pinfunction "3_3") (pintype "passive"))
      (node (ref "U1") (pin "43") (pinfunction "JTAG_TDI/PA15_43") (pintype "bidirectional"))
    )
    (net (code "36") (name "PBR{slash}TMS") (class "Default")
      (node (ref "JTAG") (pin "1") (pinfunction "1_1") (pintype "bidirectional"))
      (node (ref "S2") (pin "3") (pinfunction "3_3") (pintype "passive"))
      (node (ref "U1") (pin "44") (pinfunction "JTAG_TMS/PA13_44") (pintype "bidirectional"))
    )
    (net (code "37") (name "RGB_BLUE") (class "Default")
      (node (ref "R11") (pin "2") (pinfunction "2_2") (pintype "passive"))
      (node (ref "U1") (pin "6") (pinfunction "GPIO_2/PA3_6") (pintype "bidirectional"))
    )
    (net (code "38") (name "RGB_GREEN") (class "Default")
      (node (ref "R10") (pin "2") (pinfunction "2_2") (pintype "passive"))
      (node (ref "U1") (pin "7") (pinfunction "GPIO_1/PA2_7") (pintype "bidirectional"))
    )
    (net (code "39") (name "RGB_RED") (class "Default")
      (node (ref "R9") (pin "2") (pinfunction "2_2") (pintype "passive"))
      (node (ref "U1") (pin "8") (pinfunction "GPIO_0/PA1_8") (pintype "bidirectional"))
    )
    (net (code "40") (name "RX") (class "Default")
      (node (ref "CAM") (pin "RX") (pinfunction "RX_RX") (pintype "passive"))
      (node (ref "U1") (pin "38") (pinfunction "MCU_UART_RX/PA10_38") (pintype "bidirectional"))
    )
    (net (code "41") (name "SCK") (class "Default")
      (node (ref "TP3") (pin "P$1") (pinfunction "1_P$1") (pintype "bidirectional"))
      (node (ref "U1") (pin "24") (pinfunction "SPI_SCK/PA5_24") (pintype "bidirectional"))
      (node (ref "U11") (pin "6") (pinfunction "SCK_6") (pintype "bidirectional"))
      (node (ref "U8") (pin "5") (pinfunction "SCK_5") (pintype "bidirectional"))
    )
    (net (code "42") (name "SCL") (class "Default")
      (node (ref "JP2") (pin "1") (pinfunction "1_1") (pintype "passive"))
      (node (ref "R7") (pin "1") (pinfunction "1_1") (pintype "passive"))
      (node (ref "U1") (pin "5") (pinfunction "GPIO_3/PB6_5") (pintype "bidirectional"))
      (node (ref "U4") (pin "23") (pinfunction "SCL_23") (pintype "bidirectional"))
      (node (ref "U5") (pin "SCK") (pinfunction "SCK_SCK") (pintype "input"))
      (node (ref "U6") (pin "B3") (pinfunction "SCL_B3") (pintype "bidirectional"))
      (node (ref "U7") (pin "5") (pinfunction "SCL_5") (pintype "input"))
    )
    (net (code "43") (name "SDA") (class "Default")
      (node (ref "JP2") (pin "2") (pinfunction "2_2") (pintype "passive"))
      (node (ref "R6") (pin "2") (pinfunction "2_2") (pintype "passive"))
      (node (ref "U1") (pin "4") (pinfunction "GPIO_4/PB7_4") (pintype "bidirectional"))
      (node (ref "U4") (pin "24") (pinfunction "SDA_24") (pintype "bidirectional"))
      (node (ref "U5") (pin "DATA") (pinfunction "DATA_DATA") (pintype "bidirectional"))
      (node (ref "U6") (pin "C3") (pinfunction "SDA_C3") (pintype "bidirectional"))
      (node (ref "U7") (pin "6") (pinfunction "SDA_6") (pintype "bidirectional"))
    )
    (net (code "44") (name "SD_CD{slash}TRST") (class "Default")
      (node (ref "JTAG") (pin "5") (pinfunction "5_5") (pintype "bidirectional"))
      (node (ref "U1") (pin "42") (pinfunction "~{JTAG_TRST}/PB4_42") (pintype "bidirectional"))
      (node (ref "U8") (pin "CD") (pinfunction "CD_CD") (pintype "bidirectional"))
    )
    (net (code "45") (name "SD_CS") (class "Default")
      (node (ref "TP1") (pin "P$1") (pinfunction "1_P$1") (pintype "bidirectional"))
      (node (ref "U1") (pin "22") (pinfunction "~{SPI_SS}/PA4_22") (pintype "bidirectional"))
      (node (ref "U8") (pin "2") (pinfunction "CS_2") (pintype "bidirectional"))
    )
    (net (code "46") (name "TX") (class "Default")
      (node (ref "CAM") (pin "TX") (pinfunction "TX_TX") (pintype "passive"))
      (node (ref "U1") (pin "39") (pinfunction "MCU_UART_TX/PA9_39") (pintype "bidirectional"))
    )
    (net (code "47") (name "UVCC") (class "Default")
      (node (ref "C7") (pin "2") (pinfunction "2_2") (pintype "passive"))
      (node (ref "JP1") (pin "1") (pinfunction "VCC_1") (pintype "input"))
      (node (ref "LED") (pin "A@1") (pinfunction "A_A@1") (pintype "passive"))
      (node (ref "U2") (pin "4") (pinfunction "VDD_4") (pintype "power_in"))
    )
    (net (code "48") (name "VBAT") (class "Default")
      (node (ref "BAT") (pin "+") (pinfunction "+_+") (pintype "passive"))
      (node (ref "C10") (pin "2") (pinfunction "2_2") (pintype "passive"))
      (node (ref "SW") (pin "2") (pinfunction "2_2") (pintype "bidirectional"))
      (node (ref "U2") (pin "3") (pinfunction "VBAT_3") (pintype "output"))
    )
    (net (code "49") (name "WKP") (class "Default")
      (node (ref "R19") (pin "2") (pinfunction "2_2") (pintype "passive"))
      (node (ref "U1") (pin "27") (pinfunction "MCU_WKUP_27") (pintype "bidirectional"))
      (node (ref "U4") (pin "12") (pinfunction "INT_12") (pintype "bidirectional"))
    )
    (net (code "50") (name "unconnected-(JP1-ID-Pad4)") (class "Default")
      (node (ref "JP1") (pin "4") (pinfunction "ID_4") (pintype "input"))
    )
    (net (code "51") (name "unconnected-(S1-Pad4)") (class "Default")
      (node (ref "S1") (pin "4") (pinfunction "4_4") (pintype "passive"))
    )
    (net (code "52") (name "unconnected-(S2-Pad4)") (class "Default")
      (node (ref "S2") (pin "4") (pinfunction "4_4") (pintype "passive"))
    )
    (net (code "53") (name "unconnected-(U1-BTCX_RF_ACTIVE-Pad9)") (class "Default")
      (node (ref "U1") (pin "9") (pinfunction "BTCX_RF_ACTIVE_9") (pintype "bidirectional"))
    )
    (net (code "54") (name "unconnected-(U1-BTCX_STATUS-Pad10)") (class "Default")
      (node (ref "U1") (pin "10") (pinfunction "BTCX_STATUS_10") (pintype "bidirectional"))
    )
    (net (code "55") (name "unconnected-(U1-BTCX_TXCONF-Pad11)") (class "Default")
      (node (ref "U1") (pin "11") (pinfunction "BTCX_TXCONF_11") (pintype "bidirectional"))
    )
    (net (code "56") (name "unconnected-(U1-NC-Pad31)") (class "Default")
      (node (ref "U1") (pin "31") (pinfunction "NC_31") (pintype "bidirectional"))
    )
    (net (code "57") (name "unconnected-(U1-NC-Pad32)") (class "Default")
      (node (ref "U1") (pin "32") (pinfunction "NC_32") (pintype "bidirectional"))
    )
    (net (code "58") (name "unconnected-(U1-NC-Pad33)") (class "Default")
      (node (ref "U1") (pin "33") (pinfunction "NC_33") (pintype "bidirectional"))
    )
    (net (code "59") (name "unconnected-(U1-NC-Pad34)") (class "Default")
      (node (ref "U1") (pin "34") (pinfunction "NC_34") (pintype "bidirectional"))
    )
    (net (code "60") (name "unconnected-(U1-NC-Pad35)") (class "Default")
      (node (ref "U1") (pin "35") (pinfunction "NC_35") (pintype "bidirectional"))
    )
    (net (code "61") (name "unconnected-(U1-NC-Pad36)") (class "Default")
      (node (ref "U1") (pin "36") (pinfunction "NC_36") (pintype "bidirectional"))
    )
    (net (code "62") (name "unconnected-(U1-RF_SW_CTRL0_ANT0-Pad13)") (class "Default")
      (node (ref "U1") (pin "13") (pinfunction "RF_SW_CTRL0_ANT0_13") (pintype "bidirectional"))
    )
    (net (code "63") (name "unconnected-(U1-RF_SW_CTRL3_ANT1-Pad12)") (class "Default")
      (node (ref "U1") (pin "12") (pinfunction "RF_SW_CTRL3_ANT1_12") (pintype "bidirectional"))
    )
    (net (code "64") (name "unconnected-(U1-VBAT-Pad28)") (class "Default")
      (node (ref "U1") (pin "28") (pinfunction "VBAT_28") (pintype "bidirectional"))
    )
    (net (code "65") (name "unconnected-(U4-CLKOUT-Pad22)") (class "Default")
      (node (ref "U4") (pin "22") (pinfunction "CLKOUT_22") (pintype "bidirectional"))
    )
    (net (code "66") (name "unconnected-(U4-E_SCL-Pad7)") (class "Default")
      (node (ref "U4") (pin "7") (pinfunction "E_SCL_7") (pintype "bidirectional"))
    )
    (net (code "67") (name "unconnected-(U4-E_SDA-Pad6)") (class "Default")
      (node (ref "U4") (pin "6") (pinfunction "E_SDA_6") (pintype "bidirectional"))
    )
    (net (code "68") (name "unconnected-(U8-NC-Pad1)") (class "Default")
      (node (ref "U8") (pin "1") (pinfunction "NC_1") (pintype "bidirectional"))
    )
    (net (code "69") (name "unconnected-(U8-PadCD1)") (class "Default")
      (node (ref "U8") (pin "CD1") (pinfunction "CD1_CD1") (pintype "bidirectional"))
    )
    (net (code "70") (name "unconnected-(U8-PadCD2)") (class "Default")
      (node (ref "U8") (pin "CD2") (pinfunction "CD2_CD2") (pintype "bidirectional"))
    )
    (net (code "71") (name "unconnected-(U8-RSV-Pad8)") (class "Default")
      (node (ref "U8") (pin "8") (pinfunction "RSV_8") (pintype "bidirectional"))
    )
    (net (code "72") (name "~{MODE}") (class "Default")
      (node (ref "S3") (pin "2") (pinfunction "2_2") (pintype "passive"))
      (node (ref "U1") (pin "53") (pinfunction "GPIO_9/PC7_53") (pintype "bidirectional"))
    )
    (net (code "73") (name "~{RST}") (class "Default")
      (node (ref "C22") (pin "2") (pinfunction "2_2") (pintype "passive"))
      (node (ref "JTAG") (pin "6") (pinfunction "6_6") (pintype "bidirectional"))
      (node (ref "R13") (pin "2") (pinfunction "2_2") (pintype "passive"))
      (node (ref "S4") (pin "2") (pinfunction "2_2") (pintype "passive"))
      (node (ref "U1") (pin "26") (pinfunction "~{MCU_RST}_26") (pintype "bidirectional"))
    )
  )
)
